# robocoon.net
KiCad netlist of a schematic drawn in EAGLE
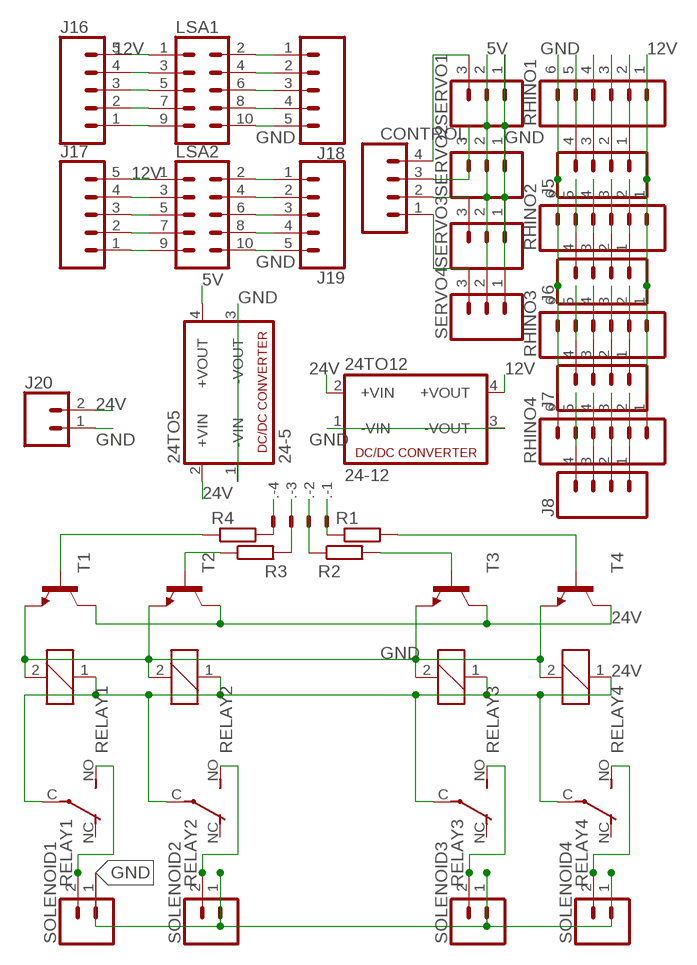
[diagram p0: schematic, sheet 1]

(export (version "E")
  (design (tool "Eeschema 10.0.6"))
  (components
    (comp (ref ".")
      (value "22-23-2041")
      (footprint "eagle-import:22-23-2041")
      (fields (field (name "MF") "MOLEX"))
      (libsource (lib "eagle-import") (part "22-23-2041"))
    )
    (comp (ref "24TO5")
      (value "24-5")
      (footprint "eagle-import:NME")
      (fields (field (name "MF") "C & D TECHNOLOGIES, INC") (field (name "MPN") "NME1205D"))
      (libsource (lib "eagle-import") (part "NME"))
    )
    (comp (ref "24TO12")
      (value "24-12")
      (footprint "eagle-import:NME")
      (fields (field (name "MF") "C & D TECHNOLOGIES, INC") (field (name "MPN") "NME1205D"))
      (libsource (lib "eagle-import") (part "NME"))
    )
    (comp (ref "CONTROL")
      (value "CONN_04")
      (footprint "eagle-import:1X04")
      (libsource (lib "eagle-import") (part "CONN_04"))
    )
    (comp (ref "J5")
      (value "CONN_04")
      (footprint "eagle-import:1X04")
      (libsource (lib "eagle-import") (part "CONN_04"))
    )
    (comp (ref "J6")
      (value "CONN_04")
      (footprint "eagle-import:1X04")
      (libsource (lib "eagle-import") (part "CONN_04"))
    )
    (comp (ref "J7")
      (value "CONN_04")
      (footprint "eagle-import:1X04")
      (libsource (lib "eagle-import") (part "CONN_04"))
    )
    (comp (ref "J8")
      (value "CONN_04")
      (footprint "eagle-import:1X04")
      (libsource (lib "eagle-import") (part "CONN_04"))
    )
    (comp (ref "J16")
      (value "CONN_05SCREW")
      (footprint "eagle-import:SCREWTERMINAL-3.5MM-5")
      (libsource (lib "eagle-import") (part "CONN_05SCREW"))
    )
    (comp (ref "J17")
      (value "CONN_05SCREW")
      (footprint "eagle-import:SCREWTERMINAL-3.5MM-5")
      (libsource (lib "eagle-import") (part "CONN_05SCREW"))
    )
    (comp (ref "J18")
      (value "CONN_05SCREW")
      (footprint "eagle-import:SCREWTERMINAL-3.5MM-5")
      (libsource (lib "eagle-import") (part "CONN_05SCREW"))
    )
    (comp (ref "J19")
      (value "CONN_05SCREW")
      (footprint "eagle-import:SCREWTERMINAL-3.5MM-5")
      (libsource (lib "eagle-import") (part "CONN_05SCREW"))
    )
    (comp (ref "J20")
      (value "CONN_023.5MM")
      (footprint "eagle-import:SCREWTERMINAL-3.5MM-2")
      (libsource (lib "eagle-import") (part "CONN_023.5MM"))
    )
    (comp (ref "LSA1")
      (value "CONN_05X2PTH")
      (footprint "eagle-import:2X5")
      (libsource (lib "eagle-import") (part "CONN_05X2PTH"))
    )
    (comp (ref "LSA2")
      (value "CONN_05X2PTH")
      (footprint "eagle-import:2X5")
      (libsource (lib "eagle-import") (part "CONN_05X2PTH"))
    )
    (comp (ref "R1")
      (value "R-EU_0204/2V")
      (footprint "eagle-import:0204V")
      (libsource (lib "eagle-import") (part "R-EU_0204/2V"))
    )
    (comp (ref "R2")
      (value "R-EU_0204/2V")
      (footprint "eagle-import:0204V")
      (libsource (lib "eagle-import") (part "R-EU_0204/2V"))
    )
    (comp (ref "R3")
      (value "R-EU_0204/2V")
      (footprint "eagle-import:0204V")
      (libsource (lib "eagle-import") (part "R-EU_0204/2V"))
    )
    (comp (ref "R4")
      (value "R-EU_0204/2V")
      (footprint "eagle-import:0204V")
      (libsource (lib "eagle-import") (part "R-EU_0204/2V"))
    )
    (comp (ref "RELAY1")
      (value "CQ1-12V")
      (footprint "eagle-import:CQ1")
      (libsource (lib "eagle-import") (part "CQ1-12V"))
    )
    (comp (ref "RELAY2")
      (value "CQ1-12V")
      (footprint "eagle-import:CQ1")
      (libsource (lib "eagle-import") (part "CQ1-12V"))
    )
    (comp (ref "RELAY3")
      (value "CQ1-12V")
      (footprint "eagle-import:CQ1")
      (libsource (lib "eagle-import") (part "CQ1-12V"))
    )
    (comp (ref "RELAY4")
      (value "CQ1-12V")
      (footprint "eagle-import:CQ1")
      (libsource (lib "eagle-import") (part "CQ1-12V"))
    )
    (comp (ref "RHINO1")
      (value "CONN_06NO_SILK_FEMALE_PTH")
      (footprint "eagle-import:1X06_NO_SILK")
      (libsource (lib "eagle-import") (part "CONN_06NO_SILK_FEMALE_PTH"))
    )
    (comp (ref "RHINO2")
      (value "CONN_06NO_SILK_FEMALE_PTH")
      (footprint "eagle-import:1X06_NO_SILK")
      (libsource (lib "eagle-import") (part "CONN_06NO_SILK_FEMALE_PTH"))
    )
    (comp (ref "RHINO3")
      (value "CONN_06NO_SILK_FEMALE_PTH")
      (footprint "eagle-import:1X06_NO_SILK")
      (libsource (lib "eagle-import") (part "CONN_06NO_SILK_FEMALE_PTH"))
    )
    (comp (ref "RHINO4")
      (value "CONN_06NO_SILK_FEMALE_PTH")
      (footprint "eagle-import:1X06_NO_SILK")
      (libsource (lib "eagle-import") (part "CONN_06NO_SILK_FEMALE_PTH"))
    )
    (comp (ref "SERVO1")
      (value "CONN_03SCREW")
      (footprint "eagle-import:SCREWTERMINAL-3.5MM-3")
      (libsource (lib "eagle-import") (part "CONN_03SCREW"))
    )
    (comp (ref "SERVO2")
      (value "CONN_03SCREW")
      (footprint "eagle-import:SCREWTERMINAL-3.5MM-3")
      (libsource (lib "eagle-import") (part "CONN_03SCREW"))
    )
    (comp (ref "SERVO3")
      (value "CONN_03SCREW")
      (footprint "eagle-import:SCREWTERMINAL-3.5MM-3")
      (libsource (lib "eagle-import") (part "CONN_03SCREW"))
    )
    (comp (ref "SERVO4")
      (value "CONN_03SCREW")
      (footprint "eagle-import:SCREWTERMINAL-3.5MM-3")
      (libsource (lib "eagle-import") (part "CONN_03SCREW"))
    )
    (comp (ref "SOLENOID1")
      (value "CONN_023.5MM")
      (footprint "eagle-import:SCREWTERMINAL-3.5MM-2")
      (libsource (lib "eagle-import") (part "CONN_023.5MM"))
    )
    (comp (ref "SOLENOID2")
      (value "CONN_023.5MM")
      (footprint "eagle-import:SCREWTERMINAL-3.5MM-2")
      (libsource (lib "eagle-import") (part "CONN_023.5MM"))
    )
    (comp (ref "SOLENOID3")
      (value "CONN_023.5MM")
      (footprint "eagle-import:SCREWTERMINAL-3.5MM-2")
      (libsource (lib "eagle-import") (part "CONN_023.5MM"))
    )
    (comp (ref "SOLENOID4")
      (value "CONN_023.5MM")
      (footprint "eagle-import:SCREWTERMINAL-3.5MM-2")
      (libsource (lib "eagle-import") (part "CONN_023.5MM"))
    )
    (comp (ref "T1")
      (value "-NPN-TO92")
      (footprint "eagle-import:TO92")
      (libsource (lib "eagle-import") (part "-NPN-TO92"))
    )
    (comp (ref "T2")
      (value "-NPN-TO92")
      (footprint "eagle-import:TO92")
      (libsource (lib "eagle-import") (part "-NPN-TO92"))
    )
    (comp (ref "T3")
      (value "-NPN-TO92")
      (footprint "eagle-import:TO92")
      (libsource (lib "eagle-import") (part "-NPN-TO92"))
    )
    (comp (ref "T4")
      (value "-NPN-TO92")
      (footprint "eagle-import:TO92")
      (libsource (lib "eagle-import") (part "-NPN-TO92"))
    )
  )
  (nets
    (net (code "1") (name "/5V") (class "Default")
      (node (ref "24TO5") (pin "4") (pinfunction "+VOUT_4") (pintype "passive"))
      (node (ref "SERVO1") (pin "2") (pinfunction "2_2") (pintype "passive"))
      (node (ref "SERVO2") (pin "2") (pinfunction "2_2") (pintype "passive"))
      (node (ref "SERVO3") (pin "2") (pinfunction "2_2") (pintype "passive"))
      (node (ref "SERVO4") (pin "2") (pinfunction "2_2") (pintype "passive"))
    )
    (net (code "2") (name "/12V") (class "Default")
      (node (ref "24TO12") (pin "4") (pinfunction "+VOUT_4") (pintype "passive"))
      (node (ref "J16") (pin "5") (pinfunction "5_5") (pintype "passive"))
      (node (ref "J17") (pin "5") (pinfunction "5_5") (pintype "passive"))
      (node (ref "LSA1") (pin "1") (pinfunction "1_1") (pintype "passive"))
      (node (ref "LSA2") (pin "1") (pinfunction "1_1") (pintype "passive"))
      (node (ref "RHINO1") (pin "1") (pinfunction "1_1") (pintype "passive"))
      (node (ref "RHINO2") (pin "1") (pinfunction "1_1") (pintype "passive"))
      (node (ref "RHINO3") (pin "1") (pinfunction "1_1") (pintype "passive"))
      (node (ref "RHINO4") (pin "1") (pinfunction "1_1") (pintype "passive"))
    )
    (net (code "3") (name "/24V") (class "Default")
      (node (ref "24TO12") (pin "2") (pinfunction "+VIN_2") (pintype "passive"))
      (node (ref "24TO5") (pin "2") (pinfunction "+VIN_2") (pintype "passive"))
      (node (ref "J20") (pin "2") (pinfunction "2_2") (pintype "passive"))
      (node (ref "RELAY1") (pin "1") (pinfunction "1_1") (pintype "passive"))
      (node (ref "RELAY1") (pin "C") (pinfunction "P_C") (pintype "passive"))
      (node (ref "RELAY2") (pin "1") (pinfunction "1_1") (pintype "passive"))
      (node (ref "RELAY2") (pin "C") (pinfunction "P_C") (pintype "passive"))
      (node (ref "RELAY3") (pin "1") (pinfunction "1_1") (pintype "passive"))
      (node (ref "RELAY3") (pin "C") (pinfunction "P_C") (pintype "passive"))
      (node (ref "RELAY4") (pin "1") (pinfunction "1_1") (pintype "passive"))
      (node (ref "RELAY4") (pin "C") (pinfunction "P_C") (pintype "passive"))
      (node (ref "T1") (pin "3") (pinfunction "C_3") (pintype "passive"))
      (node (ref "T2") (pin "3") (pinfunction "C_3") (pintype "passive"))
      (node (ref "T3") (pin "3") (pinfunction "C_3") (pintype "passive"))
      (node (ref "T4") (pin "3") (pinfunction "C_3") (pintype "passive"))
    )
    (net (code "4") (name "GND") (class "Default")
      (node (ref "24TO12") (pin "1") (pinfunction "-VIN_1") (pintype "passive"))
      (node (ref "24TO12") (pin "3") (pinfunction "-VOUT_3") (pintype "passive"))
      (node (ref "24TO5") (pin "1") (pinfunction "-VIN_1") (pintype "passive"))
      (node (ref "24TO5") (pin "3") (pinfunction "-VOUT_3") (pintype "passive"))
      (node (ref "J18") (pin "5") (pinfunction "5_5") (pintype "passive"))
      (node (ref "J19") (pin "5") (pinfunction "5_5") (pintype "passive"))
      (node (ref "J20") (pin "1") (pinfunction "1_1") (pintype "passive"))
      (node (ref "LSA1") (pin "10") (pinfunction "10_10") (pintype "passive"))
      (node (ref "LSA2") (pin "10") (pinfunction "10_10") (pintype "passive"))
      (node (ref "RELAY1") (pin "2") (pinfunction "2_2") (pintype "passive"))
      (node (ref "RELAY2") (pin "2") (pinfunction "2_2") (pintype "passive"))
      (node (ref "RELAY3") (pin "2") (pinfunction "2_2") (pintype "passive"))
      (node (ref "RELAY4") (pin "2") (pinfunction "2_2") (pintype "passive"))
      (node (ref "RHINO1") (pin "6") (pinfunction "6_6") (pintype "passive"))
      (node (ref "RHINO2") (pin "6") (pinfunction "6_6") (pintype "passive"))
      (node (ref "RHINO3") (pin "6") (pinfunction "6_6") (pintype "passive"))
      (node (ref "RHINO4") (pin "6") (pinfunction "6_6") (pintype "passive"))
      (node (ref "SERVO1") (pin "1") (pinfunction "1_1") (pintype "passive"))
      (node (ref "SERVO2") (pin "1") (pinfunction "1_1") (pintype "passive"))
      (node (ref "SERVO3") (pin "1") (pinfunction "1_1") (pintype "passive"))
      (node (ref "SERVO4") (pin "1") (pinfunction "1_1") (pintype "passive"))
      (node (ref "SOLENOID1") (pin "1") (pinfunction "1_1") (pintype "passive"))
      (node (ref "SOLENOID2") (pin "1") (pinfunction "1_1") (pintype "passive"))
      (node (ref "SOLENOID3") (pin "1") (pinfunction "1_1") (pintype "passive"))
      (node (ref "SOLENOID4") (pin "1") (pinfunction "1_1") (pintype "passive"))
      (node (ref "T1") (pin "1") (pinfunction "E_1") (pintype "passive"))
      (node (ref "T2") (pin "1") (pinfunction "E_1") (pintype "passive"))
      (node (ref "T3") (pin "1") (pinfunction "E_1") (pintype "passive"))
      (node (ref "T4") (pin "1") (pinfunction "E_1") (pintype "passive"))
    )
    (net (code "5") (name "Net-(.A-S)") (class "Default")
      (node (ref ".") (pin "1") (pinfunction "S_1") (pintype "passive"))
      (node (ref "R1") (pin "1") (pinfunction "1_1") (pintype "passive"))
    )
    (net (code "6") (name "Net-(.B-S)") (class "Default")
      (node (ref ".") (pin "2") (pinfunction "S_2") (pintype "passive"))
      (node (ref "R2") (pin "1") (pinfunction "1_1") (pintype "passive"))
    )
    (net (code "7") (name "Net-(.C-S)") (class "Default")
      (node (ref ".") (pin "3") (pinfunction "S_3") (pintype "passive"))
      (node (ref "R3") (pin "2") (pinfunction "2_2") (pintype "passive"))
    )
    (net (code "8") (name "Net-(.D-S)") (class "Default")
      (node (ref ".") (pin "4") (pinfunction "S_4") (pintype "passive"))
      (node (ref "R4") (pin "2") (pinfunction "2_2") (pintype "passive"))
    )
    (net (code "9") (name "Net-(CONTROL-Pad1)") (class "Default")
      (node (ref "CONTROL") (pin "1") (pinfunction "1_1") (pintype "passive"))
      (node (ref "SERVO4") (pin "3") (pinfunction "3_3") (pintype "passive"))
    )
    (net (code "10") (name "Net-(CONTROL-Pad2)") (class "Default")
      (node (ref "CONTROL") (pin "2") (pinfunction "2_2") (pintype "passive"))
      (node (ref "SERVO3") (pin "3") (pinfunction "3_3") (pintype "passive"))
    )
    (net (code "11") (name "Net-(CONTROL-Pad3)") (class "Default")
      (node (ref "CONTROL") (pin "3") (pinfunction "3_3") (pintype "passive"))
      (node (ref "SERVO2") (pin "3") (pinfunction "3_3") (pintype "passive"))
    )
    (net (code "12") (name "Net-(CONTROL-Pad4)") (class "Default")
      (node (ref "CONTROL") (pin "4") (pinfunction "4_4") (pintype "passive"))
      (node (ref "SERVO1") (pin "3") (pinfunction "3_3") (pintype "passive"))
    )
    (net (code "13") (name "Net-(J5-Pad1)") (class "Default")
      (node (ref "J5") (pin "1") (pinfunction "1_1") (pintype "passive"))
      (node (ref "RHINO1") (pin "2") (pinfunction "2_2") (pintype "passive"))
    )
    (net (code "14") (name "Net-(J5-Pad2)") (class "Default")
      (node (ref "J5") (pin "2") (pinfunction "2_2") (pintype "passive"))
      (node (ref "RHINO1") (pin "3") (pinfunction "3_3") (pintype "passive"))
    )
    (net (code "15") (name "Net-(J5-Pad3)") (class "Default")
      (node (ref "J5") (pin "3") (pinfunction "3_3") (pintype "passive"))
      (node (ref "RHINO1") (pin "4") (pinfunction "4_4") (pintype "passive"))
    )
    (net (code "16") (name "Net-(J5-Pad4)") (class "Default")
      (node (ref "J5") (pin "4") (pinfunction "4_4") (pintype "passive"))
      (node (ref "RHINO1") (pin "5") (pinfunction "5_5") (pintype "passive"))
    )
    (net (code "17") (name "Net-(J6-Pad1)") (class "Default")
      (node (ref "J6") (pin "1") (pinfunction "1_1") (pintype "passive"))
      (node (ref "RHINO2") (pin "2") (pinfunction "2_2") (pintype "passive"))
    )
    (net (code "18") (name "Net-(J6-Pad2)") (class "Default")
      (node (ref "J6") (pin "2") (pinfunction "2_2") (pintype "passive"))
      (node (ref "RHINO2") (pin "3") (pinfunction "3_3") (pintype "passive"))
    )
    (net (code "19") (name "Net-(J6-Pad3)") (class "Default")
      (node (ref "J6") (pin "3") (pinfunction "3_3") (pintype "passive"))
      (node (ref "RHINO2") (pin "4") (pinfunction "4_4") (pintype "passive"))
    )
    (net (code "20") (name "Net-(J6-Pad4)") (class "Default")
      (node (ref "J6") (pin "4") (pinfunction "4_4") (pintype "passive"))
      (node (ref "RHINO2") (pin "5") (pinfunction "5_5") (pintype "passive"))
    )
    (net (code "21") (name "Net-(J7-Pad1)") (class "Default")
      (node (ref "J7") (pin "1") (pinfunction "1_1") (pintype "passive"))
      (node (ref "RHINO3") (pin "2") (pinfunction "2_2") (pintype "passive"))
    )
    (net (code "22") (name "Net-(J7-Pad2)") (class "Default")
      (node (ref "J7") (pin "2") (pinfunction "2_2") (pintype "passive"))
      (node (ref "RHINO3") (pin "3") (pinfunction "3_3") (pintype "passive"))
    )
    (net (code "23") (name "Net-(J7-Pad3)") (class "Default")
      (node (ref "J7") (pin "3") (pinfunction "3_3") (pintype "passive"))
      (node (ref "RHINO3") (pin "4") (pinfunction "4_4") (pintype "passive"))
    )
    (net (code "24") (name "Net-(J7-Pad4)") (class "Default")
      (node (ref "J7") (pin "4") (pinfunction "4_4") (pintype "passive"))
      (node (ref "RHINO3") (pin "5") (pinfunction "5_5") (pintype "passive"))
    )
    (net (code "25") (name "Net-(J8-Pad1)") (class "Default")
      (node (ref "J8") (pin "1") (pinfunction "1_1") (pintype "passive"))
      (node (ref "RHINO4") (pin "2") (pinfunction "2_2") (pintype "passive"))
    )
    (net (code "26") (name "Net-(J8-Pad2)") (class "Default")
      (node (ref "J8") (pin "2") (pinfunction "2_2") (pintype "passive"))
      (node (ref "RHINO4") (pin "3") (pinfunction "3_3") (pintype "passive"))
    )
    (net (code "27") (name "Net-(J8-Pad3)") (class "Default")
      (node (ref "J8") (pin "3") (pinfunction "3_3") (pintype "passive"))
      (node (ref "RHINO4") (pin "4") (pinfunction "4_4") (pintype "passive"))
    )
    (net (code "28") (name "Net-(J8-Pad4)") (class "Default")
      (node (ref "J8") (pin "4") (pinfunction "4_4") (pintype "passive"))
      (node (ref "RHINO4") (pin "5") (pinfunction "5_5") (pintype "passive"))
    )
    (net (code "29") (name "Net-(J16-Pad1)") (class "Default")
      (node (ref "J16") (pin "1") (pinfunction "1_1") (pintype "passive"))
      (node (ref "LSA1") (pin "9") (pinfunction "9_9") (pintype "passive"))
    )
    (net (code "30") (name "Net-(J16-Pad2)") (class "Default")
      (node (ref "J16") (pin "2") (pinfunction "2_2") (pintype "passive"))
      (node (ref "LSA1") (pin "7") (pinfunction "7_7") (pintype "passive"))
    )
    (net (code "31") (name "Net-(J16-Pad3)") (class "Default")
      (node (ref "J16") (pin "3") (pinfunction "3_3") (pintype "passive"))
      (node (ref "LSA1") (pin "5") (pinfunction "5_5") (pintype "passive"))
    )
    (net (code "32") (name "Net-(J16-Pad4)") (class "Default")
      (node (ref "J16") (pin "4") (pinfunction "4_4") (pintype "passive"))
      (node (ref "LSA1") (pin "3") (pinfunction "3_3") (pintype "passive"))
    )
    (net (code "33") (name "Net-(J17-Pad1)") (class "Default")
      (node (ref "J17") (pin "1") (pinfunction "1_1") (pintype "passive"))
      (node (ref "LSA2") (pin "9") (pinfunction "9_9") (pintype "passive"))
    )
    (net (code "34") (name "Net-(J17-Pad2)") (class "Default")
      (node (ref "J17") (pin "2") (pinfunction "2_2") (pintype "passive"))
      (node (ref "LSA2") (pin "7") (pinfunction "7_7") (pintype "passive"))
    )
    (net (code "35") (name "Net-(J17-Pad3)") (class "Default")
      (node (ref "J17") (pin "3") (pinfunction "3_3") (pintype "passive"))
      (node (ref "LSA2") (pin "5") (pinfunction "5_5") (pintype "passive"))
    )
    (net (code "36") (name "Net-(J17-Pad4)") (class "Default")
      (node (ref "J17") (pin "4") (pinfunction "4_4") (pintype "passive"))
      (node (ref "LSA2") (pin "3") (pinfunction "3_3") (pintype "passive"))
    )
    (net (code "37") (name "Net-(J18-Pad1)") (class "Default")
      (node (ref "J18") (pin "1") (pinfunction "1_1") (pintype "passive"))
      (node (ref "LSA1") (pin "2") (pinfunction "2_2") (pintype "passive"))
    )
    (net (code "38") (name "Net-(J18-Pad2)") (class "Default")
      (node (ref "J18") (pin "2") (pinfunction "2_2") (pintype "passive"))
      (node (ref "LSA1") (pin "4") (pinfunction "4_4") (pintype "passive"))
    )
    (net (code "39") (name "Net-(J18-Pad3)") (class "Default")
      (node (ref "J18") (pin "3") (pinfunction "3_3") (pintype "passive"))
      (node (ref "LSA1") (pin "6") (pinfunction "6_6") (pintype "passive"))
    )
    (net (code "40") (name "Net-(J18-Pad4)") (class "Default")
      (node (ref "J18") (pin "4") (pinfunction "4_4") (pintype "passive"))
      (node (ref "LSA1") (pin "8") (pinfunction "8_8") (pintype "passive"))
    )
    (net (code "41") (name "Net-(J19-Pad1)") (class "Default")
      (node (ref "J19") (pin "1") (pinfunction "1_1") (pintype "passive"))
      (node (ref "LSA2") (pin "2") (pinfunction "2_2") (pintype "passive"))
    )
    (net (code "42") (name "Net-(J19-Pad2)") (class "Default")
      (node (ref "J19") (pin "2") (pinfunction "2_2") (pintype "passive"))
      (node (ref "LSA2") (pin "4") (pinfunction "4_4") (pintype "passive"))
    )
    (net (code "43") (name "Net-(J19-Pad3)") (class "Default")
      (node (ref "J19") (pin "3") (pinfunction "3_3") (pintype "passive"))
      (node (ref "LSA2") (pin "6") (pinfunction "6_6") (pintype "passive"))
    )
    (net (code "44") (name "Net-(J19-Pad4)") (class "Default")
      (node (ref "J19") (pin "4") (pinfunction "4_4") (pintype "passive"))
      (node (ref "LSA2") (pin "8") (pinfunction "8_8") (pintype "passive"))
    )
    (net (code "45") (name "Net-(RELAY1B-S)") (class "Default")
      (node (ref "RELAY1") (pin "NO") (pinfunction "S_NO") (pintype "passive"))
      (node (ref "SOLENOID1") (pin "2") (pinfunction "2_2") (pintype "passive"))
    )
    (net (code "46") (name "Net-(RELAY2B-S)") (class "Default")
      (node (ref "RELAY2") (pin "NO") (pinfunction "S_NO") (pintype "passive"))
      (node (ref "SOLENOID2") (pin "2") (pinfunction "2_2") (pintype "passive"))
    )
    (net (code "47") (name "Net-(RELAY3B-S)") (class "Default")
      (node (ref "RELAY3") (pin "NO") (pinfunction "S_NO") (pintype "passive"))
      (node (ref "SOLENOID3") (pin "2") (pinfunction "2_2") (pintype "passive"))
    )
    (net (code "48") (name "Net-(RELAY4B-S)") (class "Default")
      (node (ref "RELAY4") (pin "NO") (pinfunction "S_NO") (pintype "passive"))
      (node (ref "SOLENOID4") (pin "2") (pinfunction "2_2") (pintype "passive"))
    )
    (net (code "49") (name "Net-(T1-B)") (class "Default")
      (node (ref "R4") (pin "1") (pinfunction "1_1") (pintype "passive"))
      (node (ref "T1") (pin "2") (pinfunction "B_2") (pintype "passive"))
    )
    (net (code "50") (name "Net-(T2-B)") (class "Default")
      (node (ref "R3") (pin "1") (pinfunction "1_1") (pintype "passive"))
      (node (ref "T2") (pin "2") (pinfunction "B_2") (pintype "passive"))
    )
    (net (code "51") (name "Net-(T3-B)") (class "Default")
      (node (ref "R2") (pin "2") (pinfunction "2_2") (pintype "passive"))
      (node (ref "T3") (pin "2") (pinfunction "B_2") (pintype "passive"))
    )
    (net (code "52") (name "Net-(T4-B)") (class "Default")
      (node (ref "R1") (pin "2") (pinfunction "2_2") (pintype "passive"))
      (node (ref "T4") (pin "2") (pinfunction "B_2") (pintype "passive"))
    )
    (net (code "53") (name "unconnected-(RELAY1B-O-PadNC)") (class "Default")
      (node (ref "RELAY1") (pin "NC") (pinfunction "O_NC") (pintype "passive"))
    )
    (net (code "54") (name "unconnected-(RELAY2B-O-PadNC)") (class "Default")
      (node (ref "RELAY2") (pin "NC") (pinfunction "O_NC") (pintype "passive"))
    )
    (net (code "55") (name "unconnected-(RELAY3B-O-PadNC)") (class "Default")
      (node (ref "RELAY3") (pin "NC") (pinfunction "O_NC") (pintype "passive"))
    )
    (net (code "56") (name "unconnected-(RELAY4B-O-PadNC)") (class "Default")
      (node (ref "RELAY4") (pin "NC") (pinfunction "O_NC") (pintype "passive"))
    )
  )
)
